# Power_supply.net
KiCad netlist of a schematic drawn in Altium Designer
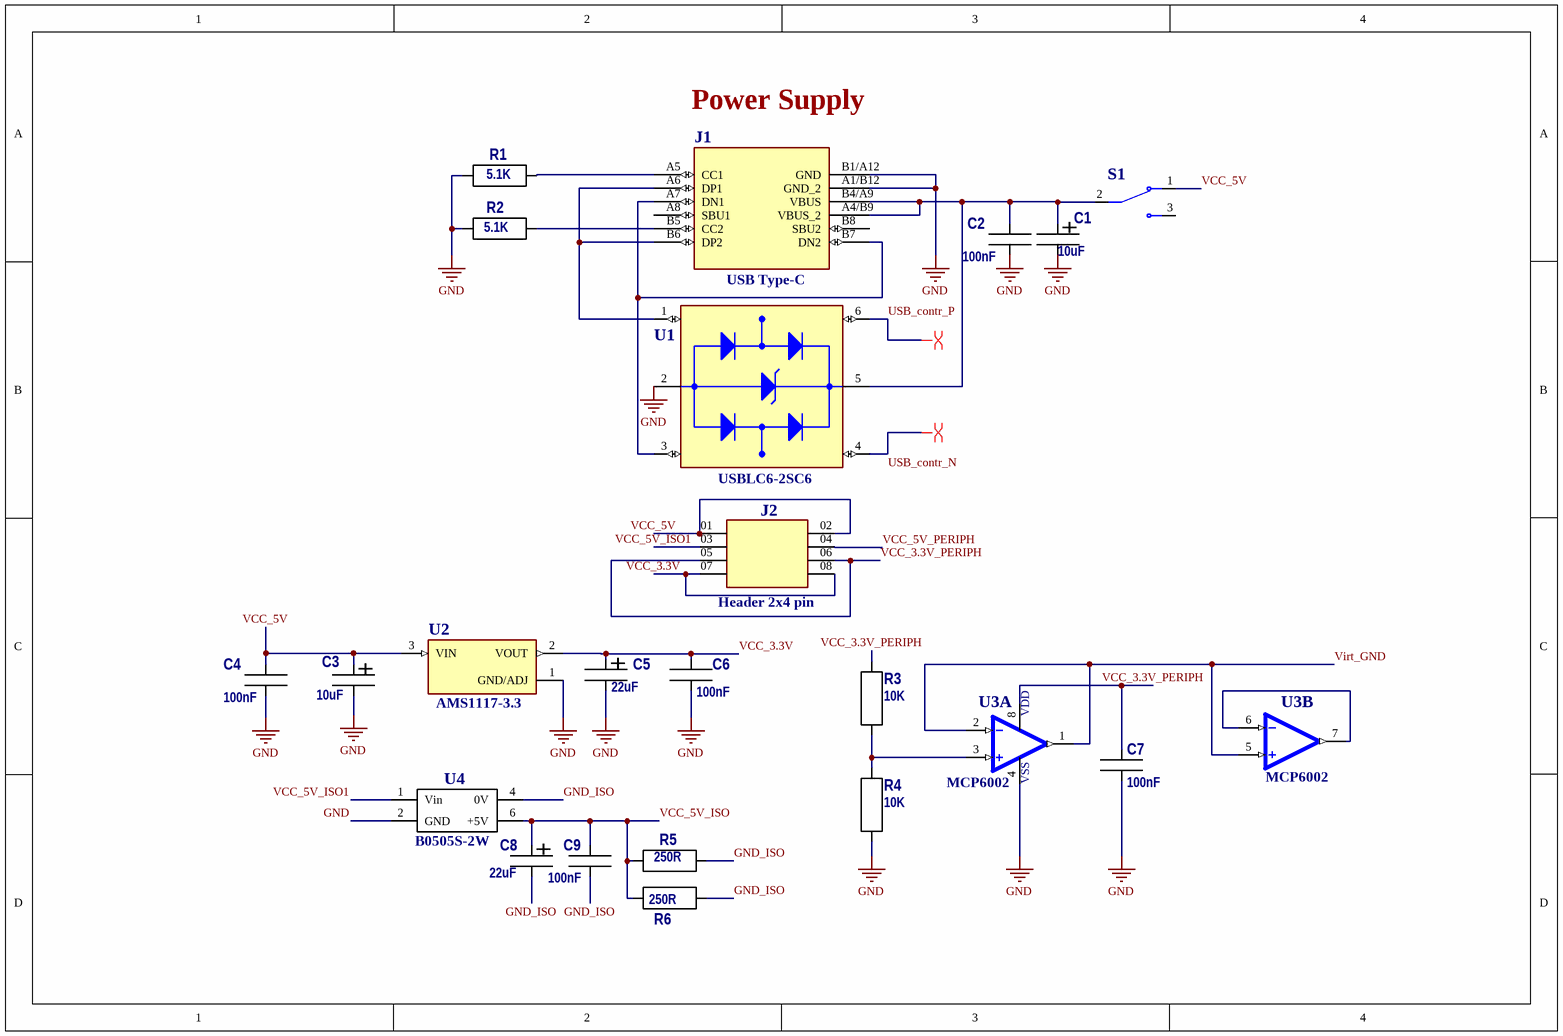
[diagram p0: Power_supply.SchDoc]

(export (version "E")
  (design (tool "Eeschema 10.0.6"))
  (components
    (comp (ref "C1")
      (value "10uF")
      (footprint "Tant B")
      (description "SMD type B 10 uF min 16V")
      (libsource (lib "RLC V7.1_BVI") (part "C T"))
    )
    (comp (ref "C2")
      (value "100nF")
      (footprint "Cap 0805 3D")
      (description "SMD 0805 100nF")
      (libsource (lib "RLC V7.1_BVI") (part "C"))
    )
    (comp (ref "C3")
      (value "10uF")
      (footprint "Tant B")
      (description "SMD type B 10 uF min 16V")
      (libsource (lib "RLC V7.1_BVI") (part "C T"))
    )
    (comp (ref "C4")
      (value "100nF")
      (footprint "Cap 0805 3D")
      (description "SMD 0805 100nF")
      (libsource (lib "RLC V7.1_BVI") (part "C"))
    )
    (comp (ref "C5")
      (value "22uF")
      (footprint "Tant B")
      (description "SMD type B 22 uF min 16V")
      (libsource (lib "RLC V7.1_BVI") (part "C T"))
    )
    (comp (ref "C6")
      (value "100nF")
      (footprint "Cap 0805 3D")
      (description "SMD 0805 100nF")
      (libsource (lib "RLC V7.1_BVI") (part "C"))
    )
    (comp (ref "C7")
      (value "100nF")
      (footprint "Cap 0805 3D")
      (description "SMD 0805 100nF")
      (libsource (lib "RLC V7.1_BVI") (part "C"))
    )
    (comp (ref "C8")
      (value "22uF")
      (footprint "Tant B")
      (description "SMD type B 22 uF min 16V")
      (libsource (lib "RLC V7.1_BVI") (part "C T"))
    )
    (comp (ref "C9")
      (value "100nF")
      (footprint "Cap 0805 3D")
      (description "SMD 0805 100nF")
      (libsource (lib "RLC V7.1_BVI") (part "C"))
    )
    (comp (ref "J1")
      (value "USB Type-C")
      (footprint "216990-0002_MOL")
      (fields (field (name "MF") "{'manufacturer': u'Molex'}") (field (name "MP") "2169900002"))
      (libsource (lib "UBS type-C") (part "2169900002"))
    )
    (comp (ref "J2")
      (value "Header 2x4 pin")
      (footprint "SAMTEC_TSW-104-08-T-D")
      (fields (field (name "MP") "TSW-104-08-T-D"))
      (libsource (lib "header 2x4 pin") (part "TSW-104-08-T-D"))
    )
    (comp (ref "R1")
      (value "5.1K")
      (footprint "Res_0805 3D")
      (description "0603 0.1%")
      (libsource (lib "RLC V7.1_BVI") (part "R"))
    )
    (comp (ref "R2")
      (value "5.1K")
      (footprint "Res_0805 3D")
      (description "0603 0.1%")
      (libsource (lib "RLC V7.1_BVI") (part "R"))
    )
    (comp (ref "R3")
      (value "10K")
      (footprint "Res_1206 3D")
      (description "0805 10K")
      (libsource (lib "RLC V7.1_BVI") (part "R"))
    )
    (comp (ref "R4")
      (value "10K")
      (footprint "Res_1206 3D")
      (description "0805 10K")
      (libsource (lib "RLC V7.1_BVI") (part "R"))
    )
    (comp (ref "R5")
      (value "250R")
      (footprint "Res_1206 3D")
      (description "0805 10K")
      (libsource (lib "RLC V7.1_BVI") (part "R"))
    )
    (comp (ref "R6")
      (value "250R")
      (footprint "Res_1206 3D")
      (description "0805 10K")
      (libsource (lib "RLC V7.1_BVI") (part "R"))
    )
    (comp (ref "S1")
      (value "STS121RA04")
      (footprint "TE_STS121RA04")
      (description "Slide Switch SPDT Through Hole, Right Angle")
      (fields (field (name "MF") "TE Connectivity"))
      (libsource (lib "STS121RA04") (part "STS121RA04"))
    )
    (comp (ref "U1")
      (value "USBLC6-2SC6")
      (footprint "SOT95P280X145-6N")
      (description "17V Clamp 5A (8/20Âµs) Ipp Tvs Diode Surface Mount SOT-23-6")
      (fields (field (name "MF") "STMicroelectronics"))
      (libsource (lib "USBLC6-2SC6") (part "USBLC6-2SC6"))
    )
    (comp (ref "U2")
      (value "AMS1117-3.3")
      (footprint "SOT229P700X180-4N")
      (description "1A LOW DROPOUT VOLTAGE REGULATOR")
      (fields (field (name "MP") "AMS1117-5.0") (field (name "MF") "ams"))
      (libsource (lib "AMS1117-5.0") (part "AMS1117-5.0"))
    )
    (comp (ref "U3")
      (value "MCP6002")
      (footprint "SOIC127P600X175-8N")
      (fields (field (name "MF") "Microchip") (field (name "MP") "MCP6002-I/SN"))
      (libsource (lib "MCP6002-I_SN") (part "MCP6002-I/SN"))
    )
    (comp (ref "U4")
      (value "B0505S-2W")
      (footprint "B0505S-2W")
      (description "Изолированный DC-DC преобразователь, вход 5В, выход 5В 3Вт")
      (libsource (lib "B0505S-2W") (part "B0505S-2W"))
    )
  )
  (nets
    (net (code "1") (name "/GND_ISO") (class "Default")
      (node (ref "C8") (pin "2") (pinfunction "-_2") (pintype "passive"))
      (node (ref "C9") (pin "2") (pintype "passive"))
      (node (ref "R5") (pin "1") (pintype "passive"))
      (node (ref "R6") (pin "1") (pintype "passive"))
      (node (ref "U4") (pin "4") (pinfunction "0V_4") (pintype "passive"))
    )
    (net (code "2") (name "/USB_contr_N") (class "Default")
      (node (ref "U1") (pin "4") (pinfunction "I/O2_OUT_4") (pintype "bidirectional"))
    )
    (net (code "3") (name "/USB_contr_P") (class "Default")
      (node (ref "U1") (pin "6") (pinfunction "I/O1_OUT_6") (pintype "bidirectional"))
    )
    (net (code "4") (name "/VCC_3.3V") (class "Default")
      (node (ref "C5") (pin "1") (pinfunction "+_1") (pintype "passive"))
      (node (ref "C6") (pin "1") (pintype "passive"))
      (node (ref "J2") (pin "07") (pinfunction "07_07") (pintype "passive"))
      (node (ref "J2") (pin "08") (pinfunction "08_08") (pintype "passive"))
      (node (ref "U2") (pin "2") (pinfunction "VOUT_2") (pintype "output"))
    )
    (net (code "5") (name "/VCC_3.3V_PERIPH") (class "Default")
      (node (ref "C7") (pin "1") (pintype "passive"))
      (node (ref "J2") (pin "05") (pinfunction "05_05") (pintype "passive"))
      (node (ref "J2") (pin "06") (pinfunction "06_06") (pintype "passive"))
      (node (ref "R3") (pin "2") (pintype "passive"))
      (node (ref "U3") (pin "8") (pinfunction "VDD_8") (pintype "power_in"))
    )
    (net (code "6") (name "/VCC_5V") (class "Default")
      (node (ref "C3") (pin "1") (pinfunction "+_1") (pintype "passive"))
      (node (ref "C4") (pin "1") (pintype "passive"))
      (node (ref "J2") (pin "01") (pinfunction "01_01") (pintype "passive"))
      (node (ref "J2") (pin "02") (pinfunction "02_02") (pintype "passive"))
      (node (ref "S1") (pin "1") (pinfunction "1_1") (pintype "passive"))
      (node (ref "U2") (pin "3") (pinfunction "VIN_3") (pintype "input"))
    )
    (net (code "7") (name "/VCC_5V_ISO") (class "Default")
      (node (ref "C8") (pin "1") (pinfunction "+_1") (pintype "passive"))
      (node (ref "C9") (pin "1") (pintype "passive"))
      (node (ref "R5") (pin "2") (pintype "passive"))
      (node (ref "R6") (pin "2") (pintype "passive"))
      (node (ref "U4") (pin "6") (pinfunction "+5V_6") (pintype "passive"))
    )
    (net (code "8") (name "/VCC_5V_ISO1") (class "Default")
      (node (ref "J2") (pin "03") (pinfunction "03_03") (pintype "passive"))
      (node (ref "U4") (pin "1") (pinfunction "Vin_1") (pintype "passive"))
    )
    (net (code "9") (name "/VCC_5V_PERIPH") (class "Default")
      (node (ref "J2") (pin "04") (pinfunction "04_04") (pintype "passive"))
    )
    (net (code "10") (name "/Virt_GND") (class "Default")
      (node (ref "U3") (pin "1") (pinfunction "VOUTA_1") (pintype "output"))
      (node (ref "U3") (pin "2") (pinfunction "VINA-_2") (pintype "input"))
      (node (ref "U3") (pin "5") (pinfunction "VINB+_5") (pintype "input"))
    )
    (net (code "11") (name "GND") (class "Default")
      (node (ref "C1") (pin "2") (pinfunction "-_2") (pintype "passive"))
      (node (ref "C2") (pin "2") (pintype "passive"))
      (node (ref "C3") (pin "2") (pinfunction "-_2") (pintype "passive"))
      (node (ref "C4") (pin "2") (pintype "passive"))
      (node (ref "C5") (pin "2") (pinfunction "-_2") (pintype "passive"))
      (node (ref "C6") (pin "2") (pintype "passive"))
      (node (ref "C7") (pin "2") (pintype "passive"))
      (node (ref "J1") (pin "A1/B12") (pinfunction "GND_2_A1/B12") (pintype "passive"))
      (node (ref "J1") (pin "B1/A12") (pinfunction "GND_B1/A12") (pintype "passive"))
      (node (ref "R1") (pin "2") (pintype "passive"))
      (node (ref "R2") (pin "2") (pintype "passive"))
      (node (ref "R4") (pin "1") (pintype "passive"))
      (node (ref "U1") (pin "2") (pinfunction "GND_2") (pintype "power_in"))
      (node (ref "U2") (pin "1") (pinfunction "GND/ADJ_1") (pintype "power_in"))
      (node (ref "U3") (pin "4") (pinfunction "VSS_4") (pintype "power_in"))
      (node (ref "U4") (pin "2") (pinfunction "GND_2") (pintype "passive"))
    )
    (net (code "12") (name "Net-(C1-+)") (class "Default")
      (node (ref "C1") (pin "1") (pinfunction "+_1") (pintype "passive"))
      (node (ref "C2") (pin "1") (pintype "passive"))
      (node (ref "J1") (pin "A4/B9") (pinfunction "VBUS_2_A4/B9") (pintype "power_in"))
      (node (ref "J1") (pin "B4/A9") (pinfunction "VBUS_B4/A9") (pintype "power_in"))
      (node (ref "S1") (pin "2") (pinfunction "2_2") (pintype "passive"))
      (node (ref "U1") (pin "5") (pinfunction "VBUS_5") (pintype "power_in"))
    )
    (net (code "13") (name "Net-(J1-CC1)") (class "Default")
      (node (ref "J1") (pin "A5") (pinfunction "CC1_A5") (pintype "bidirectional"))
      (node (ref "R1") (pin "1") (pintype "passive"))
    )
    (net (code "14") (name "Net-(J1-CC2)") (class "Default")
      (node (ref "J1") (pin "B5") (pinfunction "CC2_B5") (pintype "bidirectional"))
      (node (ref "R2") (pin "1") (pintype "passive"))
    )
    (net (code "15") (name "Net-(J1-DN1)") (class "Default")
      (node (ref "J1") (pin "A7") (pinfunction "DN1_A7") (pintype "bidirectional"))
      (node (ref "J1") (pin "B7") (pinfunction "DN2_B7") (pintype "bidirectional"))
      (node (ref "U1") (pin "3") (pinfunction "I/O2_IN_3") (pintype "bidirectional"))
    )
    (net (code "16") (name "Net-(J1-DP1)") (class "Default")
      (node (ref "J1") (pin "A6") (pinfunction "DP1_A6") (pintype "bidirectional"))
      (node (ref "J1") (pin "B6") (pinfunction "DP2_B6") (pintype "bidirectional"))
      (node (ref "U1") (pin "1") (pinfunction "I/O1_IN_1") (pintype "bidirectional"))
    )
    (net (code "17") (name "Net-(U3A-VINA+)") (class "Default")
      (node (ref "R3") (pin "1") (pintype "passive"))
      (node (ref "R4") (pin "2") (pintype "passive"))
      (node (ref "U3") (pin "3") (pinfunction "VINA+_3") (pintype "input"))
    )
    (net (code "18") (name "Net-(U3B-VINB-)") (class "Default")
      (node (ref "U3") (pin "6") (pinfunction "VINB-_6") (pintype "input"))
      (node (ref "U3") (pin "7") (pinfunction "VOUTB_7") (pintype "output"))
    )
    (net (code "19") (name "unconnected-(J1-SBU1-PadA8)") (class "Default")
      (node (ref "J1") (pin "A8") (pinfunction "SBU1_A8") (pintype "bidirectional"))
    )
    (net (code "20") (name "unconnected-(J1-SBU2-PadB8)") (class "Default")
      (node (ref "J1") (pin "B8") (pinfunction "SBU2_B8") (pintype "bidirectional"))
    )
    (net (code "21") (name "unconnected-(S1-Pad3)") (class "Default")
      (node (ref "S1") (pin "3") (pinfunction "3_3") (pintype "passive"))
    )
  )
)
